# Display.net
KiCad netlist of a schematic drawn in Altium Designer
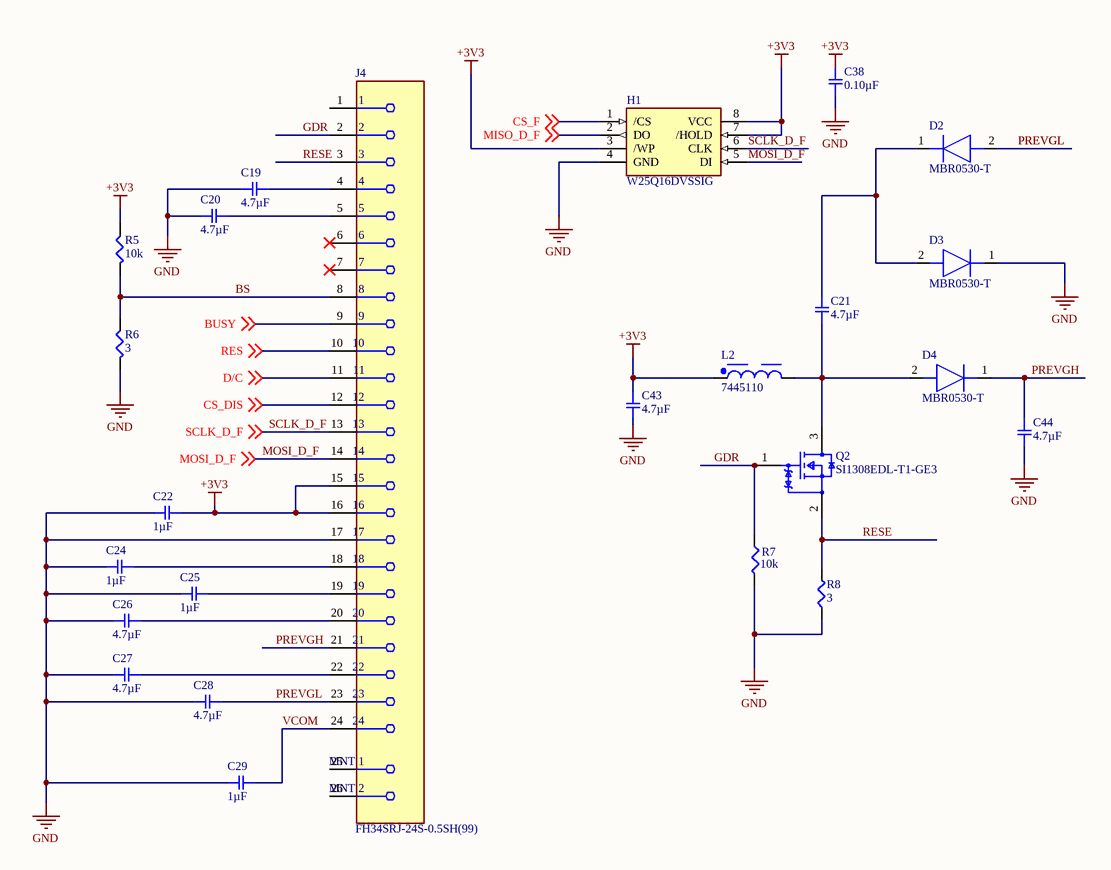
[diagram p0: Display.SchDoc]

(export (version "E")
  (design (tool "Eeschema 10.0.6"))
  (components
    (comp (ref "C19")
      (value "4.7µF")
      (footprint "SMD-0402C")
      (description "CAP CER 4.7UF 10V X5R 0402")
      (fields
        (field (name "DIGI-KEY PART NUMBER") "490-10984-1-ND")
        (field (name "PART NUMBER") "ZRB15XR61A475ME01D")
      )
      (libsource (lib "capacitor_murata_0402") (part "ZRB15XR61A475ME01D"))
    )
    (comp (ref "C20")
      (value "4.7µF")
      (footprint "SMD-0402C")
      (description "CAP CER 4.7UF 10V X5R 0402")
      (fields
        (field (name "DIGI-KEY PART NUMBER") "490-10984-1-ND")
        (field (name "PART NUMBER") "ZRB15XR61A475ME01D")
      )
      (libsource (lib "capacitor_murata_0402") (part "ZRB15XR61A475ME01D"))
    )
    (comp (ref "C21")
      (value "4.7µF")
      (footprint "SMD-0402C")
      (description "CAP CER 4.7UF 10V X5R 0402")
      (fields
        (field (name "DIGI-KEY PART NUMBER") "490-10984-1-ND")
        (field (name "PART NUMBER") "ZRB15XR61A475ME01D")
      )
      (libsource (lib "capacitor_murata_0402") (part "ZRB15XR61A475ME01D"))
    )
    (comp (ref "C22")
      (value "1µF")
      (footprint "SMD-0402C")
      (description "CAP CER 1UF 25V X5R 0402")
      (fields
        (field (name "DIGI-KEY PART NUMBER") "490-10018-1-ND")
        (field (name "PART NUMBER") "GRM155R61E105MA12D")
      )
      (libsource (lib "capacitor_murata_0402") (part "GRM155R61E105MA12D"))
    )
    (comp (ref "C24")
      (value "1µF")
      (footprint "SMD-0402C")
      (description "CAP CER 1UF 25V X5R 0402")
      (fields
        (field (name "DIGI-KEY PART NUMBER") "490-10018-1-ND")
        (field (name "PART NUMBER") "GRM155R61E105MA12D")
      )
      (libsource (lib "capacitor_murata_0402") (part "GRM155R61E105MA12D"))
    )
    (comp (ref "C25")
      (value "1µF")
      (footprint "SMD-0402C")
      (description "CAP CER 1UF 25V X5R 0402")
      (fields
        (field (name "DIGI-KEY PART NUMBER") "490-10018-1-ND")
        (field (name "PART NUMBER") "GRM155R61E105MA12D")
      )
      (libsource (lib "capacitor_murata_0402") (part "GRM155R61E105MA12D"))
    )
    (comp (ref "C26")
      (value "4.7µF")
      (footprint "SMD-0402C")
      (description "CAP CER 4.7UF 10V X5R 0402")
      (fields
        (field (name "DIGI-KEY PART NUMBER") "490-10984-1-ND")
        (field (name "PART NUMBER") "ZRB15XR61A475ME01D")
      )
      (libsource (lib "capacitor_murata_0402") (part "ZRB15XR61A475ME01D"))
    )
    (comp (ref "C27")
      (value "4.7µF")
      (footprint "SMD-0402C")
      (description "CAP CER 4.7UF 10V X5R 0402")
      (fields
        (field (name "DIGI-KEY PART NUMBER") "490-10984-1-ND")
        (field (name "PART NUMBER") "ZRB15XR61A475ME01D")
      )
      (libsource (lib "capacitor_murata_0402") (part "ZRB15XR61A475ME01D"))
    )
    (comp (ref "C28")
      (value "4.7µF")
      (footprint "SMD-0402C")
      (description "CAP CER 4.7UF 10V X5R 0402")
      (fields
        (field (name "DIGI-KEY PART NUMBER") "490-10984-1-ND")
        (field (name "PART NUMBER") "ZRB15XR61A475ME01D")
      )
      (libsource (lib "capacitor_murata_0402") (part "ZRB15XR61A475ME01D"))
    )
    (comp (ref "C29")
      (value "1µF")
      (footprint "SMD-0402C")
      (description "CAP CER 1UF 25V X5R 0402")
      (fields
        (field (name "DIGI-KEY PART NUMBER") "490-10018-1-ND")
        (field (name "PART NUMBER") "GRM155R61E105MA12D")
      )
      (libsource (lib "capacitor_murata_0402") (part "GRM155R61E105MA12D"))
    )
    (comp (ref "C38")
      (value "0.10µF")
      (footprint "SMD-0402C")
      (description "CAP CER 0.1UF 16V X7R 0402")
      (fields
        (field (name "DIGI-KEY PART NUMBER") "490-4759-1-ND")
        (field (name "PART NUMBER") "GCM155R71C104KA55D")
      )
      (libsource (lib "capacitor_murata_0402") (part "GCM155R71C104KA55D"))
    )
    (comp (ref "C43")
      (value "4.7µF")
      (footprint "SMD-0402C")
      (description "CAP CER 4.7UF 10V X5R 0402")
      (fields
        (field (name "DIGI-KEY PART NUMBER") "490-13252-1-ND")
        (field (name "PART NUMBER") "ZRB15XR61A475KE01D")
      )
      (libsource (lib "capacitor_murata_0402") (part "ZRB15XR61A475KE01D"))
    )
    (comp (ref "C44")
      (value "4.7µF")
      (footprint "SMD-0402C")
      (description "CAP CER 4.7UF 10V X5R 0402")
      (fields
        (field (name "DIGI-KEY PART NUMBER") "490-13252-1-ND")
        (field (name "PART NUMBER") "ZRB15XR61A475KE01D")
      )
      (libsource (lib "capacitor_murata_0402") (part "ZRB15XR61A475KE01D"))
    )
    (comp (ref "D2")
      (value "MBR0530-T")
      (footprint "SamacSys:SOD3716X135N")
      (description "Diode")
      (fields (field (name "MOUSER PART NUMBER") "833-MBR0530-T"))
      (libsource (lib "*") (part "MBR0530-T"))
    )
    (comp (ref "D3")
      (value "MBR0530-T")
      (footprint "SamacSys:SOD3716X135N")
      (description "Diode")
      (fields (field (name "MOUSER PART NUMBER") "833-MBR0530-T"))
      (libsource (lib "*") (part "MBR0530-T"))
    )
    (comp (ref "D4")
      (value "MBR0530-T")
      (footprint "SamacSys:SOD3716X135N")
      (description "Diode")
      (fields (field (name "MOUSER PART NUMBER") "833-MBR0530-T"))
      (libsource (lib "*") (part "MBR0530-T"))
    )
    (comp (ref "H1")
      (value "W25Q16DVSSIG")
      (footprint "SamacSys:SOIC127P790X216-8N")
      (description "Hardware")
      (libsource (lib "*") (part "W25Q16DVSSIG"))
    )
    (comp (ref "J4")
      (value "FH34SRJ-24S-0.5SH(99)")
      (footprint "FP-FH34SRJ-24S-0_5SH_99-MFG")
      (description "CONN FPC/FFC 24POS .5MM")
      (libsource (lib "Altium Content Vault") (part "affe414c170fb6748ef65fd2752df84"))
    )
    (comp (ref "L2")
      (value "7445110")
      (footprint "WE-PD3_Type S")
      (fields (field (name "TOLERANCE") "20%"))
      (libsource (lib "Altium Content Vault") (part "Inductor - 2"))
    )
    (comp (ref "Q2")
      (value "SI1308EDL-T1-GE3")
      (footprint "FP-5549-MFG")
      (description "MOSFET N-CH 30V 1.4A SC-70-3")
      (libsource (lib "Altium Content Vault") (part "e96677422f20f20903245877d22b385"))
    )
    (comp (ref "R5")
      (value "10k")
      (footprint "SMD-0402-RES")
      (description "RES SMD 10K OHM 5% 1/10W 0402")
      (fields (field (name "PART NUMBER") "ERJ-2GEJ103X") (field (name "DIGI-KEY PART NUMBER") "P10KJCT-ND"))
      (libsource (lib "Panasonic_ERJ_0402") (part "ERJ-2GEJ103X"))
    )
    (comp (ref "R6")
      (value "3")
      (footprint "SMD-0402-RES")
      (description "RES SMD 3 OHM 5% 1/10W 0402")
      (fields (field (name "PART NUMBER") "ERJ-2GEJ3R0X") (field (name "DIGI-KEY PART NUMBER") "P3.0JCT-ND"))
      (libsource (lib "Panasonic_ERJ_0402") (part "ERJ-2GEJ3R0X"))
    )
    (comp (ref "R7")
      (value "10k")
      (footprint "SMD-0402-RES")
      (description "RES SMD 10K OHM 5% 1/10W 0402")
      (fields (field (name "PART NUMBER") "ERJ-2GEJ103X") (field (name "DIGI-KEY PART NUMBER") "P10KJCT-ND"))
      (libsource (lib "Panasonic_ERJ_0402") (part "ERJ-2GEJ103X"))
    )
    (comp (ref "R8")
      (value "3")
      (footprint "SMD-0402-RES")
      (description "RES SMD 3 OHM 5% 1/10W 0402")
      (fields (field (name "PART NUMBER") "ERJ-2GEJ3R0X") (field (name "DIGI-KEY PART NUMBER") "P3.0JCT-ND"))
      (libsource (lib "Panasonic_ERJ_0402") (part "ERJ-2GEJ3R0X"))
    )
  )
  (nets
    (net (code "1") (name "+3V3") (class "Default")
      (node (ref "C22") (pin "1") (pinfunction "1_1") (pintype "passive"))
      (node (ref "C38") (pin "1") (pinfunction "1_1") (pintype "passive"))
      (node (ref "C43") (pin "1") (pinfunction "1_1") (pintype "passive"))
      (node (ref "H1") (pin "3") (pinfunction "/WP_3") (pintype "passive"))
      (node (ref "H1") (pin "7") (pinfunction "/HOLD_7") (pintype "input"))
      (node (ref "H1") (pin "8") (pinfunction "VCC_8") (pintype "power_in"))
      (node (ref "J4") (pin "15") (pinfunction "15_15") (pintype "passive"))
      (node (ref "J4") (pin "16") (pinfunction "16_16") (pintype "passive"))
      (node (ref "L2") (pin "1") (pinfunction "1_1") (pintype "passive"))
      (node (ref "R5") (pin "1") (pinfunction "1_1") (pintype "passive"))
    )
    (net (code "2") (name "/BS") (class "Default")
      (node (ref "J4") (pin "8") (pinfunction "8_8") (pintype "passive"))
      (node (ref "R5") (pin "2") (pinfunction "2_2") (pintype "passive"))
      (node (ref "R6") (pin "1") (pinfunction "1_1") (pintype "passive"))
    )
    (net (code "3") (name "/GDR") (class "Default")
      (node (ref "J4") (pin "2") (pinfunction "2_2") (pintype "passive"))
      (node (ref "Q2") (pin "1") (pinfunction "G_1") (pintype "passive"))
      (node (ref "R7") (pin "1") (pinfunction "1_1") (pintype "passive"))
    )
    (net (code "4") (name "/PREVGH") (class "Default")
      (node (ref "C44") (pin "1") (pinfunction "1_1") (pintype "passive"))
      (node (ref "D4") (pin "1") (pinfunction "K_1") (pintype "passive"))
      (node (ref "J4") (pin "21") (pinfunction "21_21") (pintype "passive"))
    )
    (net (code "5") (name "/PREVGL") (class "Default")
      (node (ref "C28") (pin "1") (pinfunction "1_1") (pintype "passive"))
      (node (ref "D2") (pin "2") (pinfunction "A_2") (pintype "passive"))
      (node (ref "J4") (pin "23") (pinfunction "23_23") (pintype "passive"))
    )
    (net (code "6") (name "/RESE") (class "Default")
      (node (ref "J4") (pin "3") (pinfunction "3_3") (pintype "passive"))
      (node (ref "Q2") (pin "2") (pinfunction "S_2") (pintype "passive"))
      (node (ref "R8") (pin "2") (pinfunction "2_2") (pintype "passive"))
    )
    (net (code "7") (name "/VCOM") (class "Default")
      (node (ref "C29") (pin "1") (pinfunction "1_1") (pintype "passive"))
      (node (ref "J4") (pin "24") (pinfunction "24_24") (pintype "passive"))
    )
    (net (code "8") (name "BUSY") (class "Default")
      (node (ref "J4") (pin "9") (pinfunction "9_9") (pintype "passive"))
    )
    (net (code "9") (name "CS_DIS") (class "Default")
      (node (ref "J4") (pin "12") (pinfunction "12_12") (pintype "passive"))
    )
    (net (code "10") (name "CS_F") (class "Default")
      (node (ref "H1") (pin "1") (pinfunction "/CS_1") (pintype "input"))
    )
    (net (code "11") (name "D{slash}C") (class "Default")
      (node (ref "J4") (pin "11") (pinfunction "11_11") (pintype "passive"))
    )
    (net (code "12") (name "GND") (class "Default")
      (node (ref "C19") (pin "2") (pinfunction "2_2") (pintype "passive"))
      (node (ref "C20") (pin "2") (pinfunction "2_2") (pintype "passive"))
      (node (ref "C22") (pin "2") (pinfunction "2_2") (pintype "passive"))
      (node (ref "C24") (pin "2") (pinfunction "2_2") (pintype "passive"))
      (node (ref "C25") (pin "2") (pinfunction "2_2") (pintype "passive"))
      (node (ref "C26") (pin "2") (pinfunction "2_2") (pintype "passive"))
      (node (ref "C27") (pin "2") (pinfunction "2_2") (pintype "passive"))
      (node (ref "C28") (pin "2") (pinfunction "2_2") (pintype "passive"))
      (node (ref "C29") (pin "2") (pinfunction "2_2") (pintype "passive"))
      (node (ref "C38") (pin "2") (pinfunction "2_2") (pintype "passive"))
      (node (ref "C43") (pin "2") (pinfunction "2_2") (pintype "passive"))
      (node (ref "C44") (pin "2") (pinfunction "2_2") (pintype "passive"))
      (node (ref "D3") (pin "1") (pinfunction "K_1") (pintype "passive"))
      (node (ref "H1") (pin "4") (pinfunction "GND_4") (pintype "power_in"))
      (node (ref "J4") (pin "17") (pinfunction "17_17") (pintype "passive"))
      (node (ref "R6") (pin "2") (pinfunction "2_2") (pintype "passive"))
      (node (ref "R7") (pin "2") (pinfunction "2_2") (pintype "passive"))
      (node (ref "R8") (pin "1") (pinfunction "1_1") (pintype "passive"))
    )
    (net (code "13") (name "MISO_D_F") (class "Default")
      (node (ref "H1") (pin "2") (pinfunction "DO_2") (pintype "output"))
    )
    (net (code "14") (name "MOSI_D_F") (class "Default")
      (node (ref "H1") (pin "5") (pinfunction "DI_5") (pintype "input"))
      (node (ref "J4") (pin "14") (pinfunction "14_14") (pintype "passive"))
    )
    (net (code "15") (name "Net-(C19-Pad1)") (class "Default")
      (node (ref "C19") (pin "1") (pinfunction "1_1") (pintype "passive"))
      (node (ref "J4") (pin "4") (pinfunction "4_4") (pintype "passive"))
    )
    (net (code "16") (name "Net-(C20-Pad1)") (class "Default")
      (node (ref "C20") (pin "1") (pinfunction "1_1") (pintype "passive"))
      (node (ref "J4") (pin "5") (pinfunction "5_5") (pintype "passive"))
    )
    (net (code "17") (name "Net-(C24-Pad1)") (class "Default")
      (node (ref "C24") (pin "1") (pinfunction "1_1") (pintype "passive"))
      (node (ref "J4") (pin "18") (pinfunction "18_18") (pintype "passive"))
    )
    (net (code "18") (name "Net-(C25-Pad1)") (class "Default")
      (node (ref "C25") (pin "1") (pinfunction "1_1") (pintype "passive"))
      (node (ref "J4") (pin "19") (pinfunction "19_19") (pintype "passive"))
    )
    (net (code "19") (name "Net-(C26-Pad1)") (class "Default")
      (node (ref "C26") (pin "1") (pinfunction "1_1") (pintype "passive"))
      (node (ref "J4") (pin "20") (pinfunction "20_20") (pintype "passive"))
    )
    (net (code "20") (name "Net-(C27-Pad1)") (class "Default")
      (node (ref "C27") (pin "1") (pinfunction "1_1") (pintype "passive"))
      (node (ref "J4") (pin "22") (pinfunction "22_22") (pintype "passive"))
    )
    (net (code "21") (name "Net-(D2-K)") (class "Default")
      (node (ref "C21") (pin "2") (pinfunction "2_2") (pintype "passive"))
      (node (ref "D2") (pin "1") (pinfunction "K_1") (pintype "passive"))
      (node (ref "D3") (pin "2") (pinfunction "A_2") (pintype "passive"))
    )
    (net (code "22") (name "Net-(D4-A)") (class "Default")
      (node (ref "C21") (pin "1") (pinfunction "1_1") (pintype "passive"))
      (node (ref "D4") (pin "2") (pinfunction "A_2") (pintype "passive"))
      (node (ref "L2") (pin "2") (pinfunction "2_2") (pintype "passive"))
      (node (ref "Q2") (pin "3") (pinfunction "D_3") (pintype "passive"))
    )
    (net (code "23") (name "RES") (class "Default")
      (node (ref "J4") (pin "10") (pinfunction "10_10") (pintype "passive"))
    )
    (net (code "24") (name "SCLK_D_F") (class "Default")
      (node (ref "H1") (pin "6") (pinfunction "CLK_6") (pintype "input"))
      (node (ref "J4") (pin "13") (pinfunction "13_13") (pintype "passive"))
    )
    (net (code "25") (name "unconnected-(J4-MNT_1-Pad25)") (class "Default")
      (node (ref "J4") (pin "25") (pinfunction "MNT_1_25") (pintype "passive"))
    )
    (net (code "26") (name "unconnected-(J4-MNT_2-Pad26)") (class "Default")
      (node (ref "J4") (pin "26") (pinfunction "MNT_2_26") (pintype "passive"))
    )
    (net (code "27") (name "unconnected-(J4-Pad1)") (class "Default")
      (node (ref "J4") (pin "1") (pinfunction "1_1") (pintype "passive"))
    )
    (net (code "28") (name "unconnected-(J4-Pad6)") (class "Default")
      (node (ref "J4") (pin "6") (pinfunction "6_6") (pintype "passive+no_connect"))
    )
    (net (code "29") (name "unconnected-(J4-Pad7)") (class "Default")
      (node (ref "J4") (pin "7") (pinfunction "7_7") (pintype "passive+no_connect"))
    )
  )
)
